# Dveri_Termotunnel.net
KiCad netlist of a schematic drawn in EAGLE
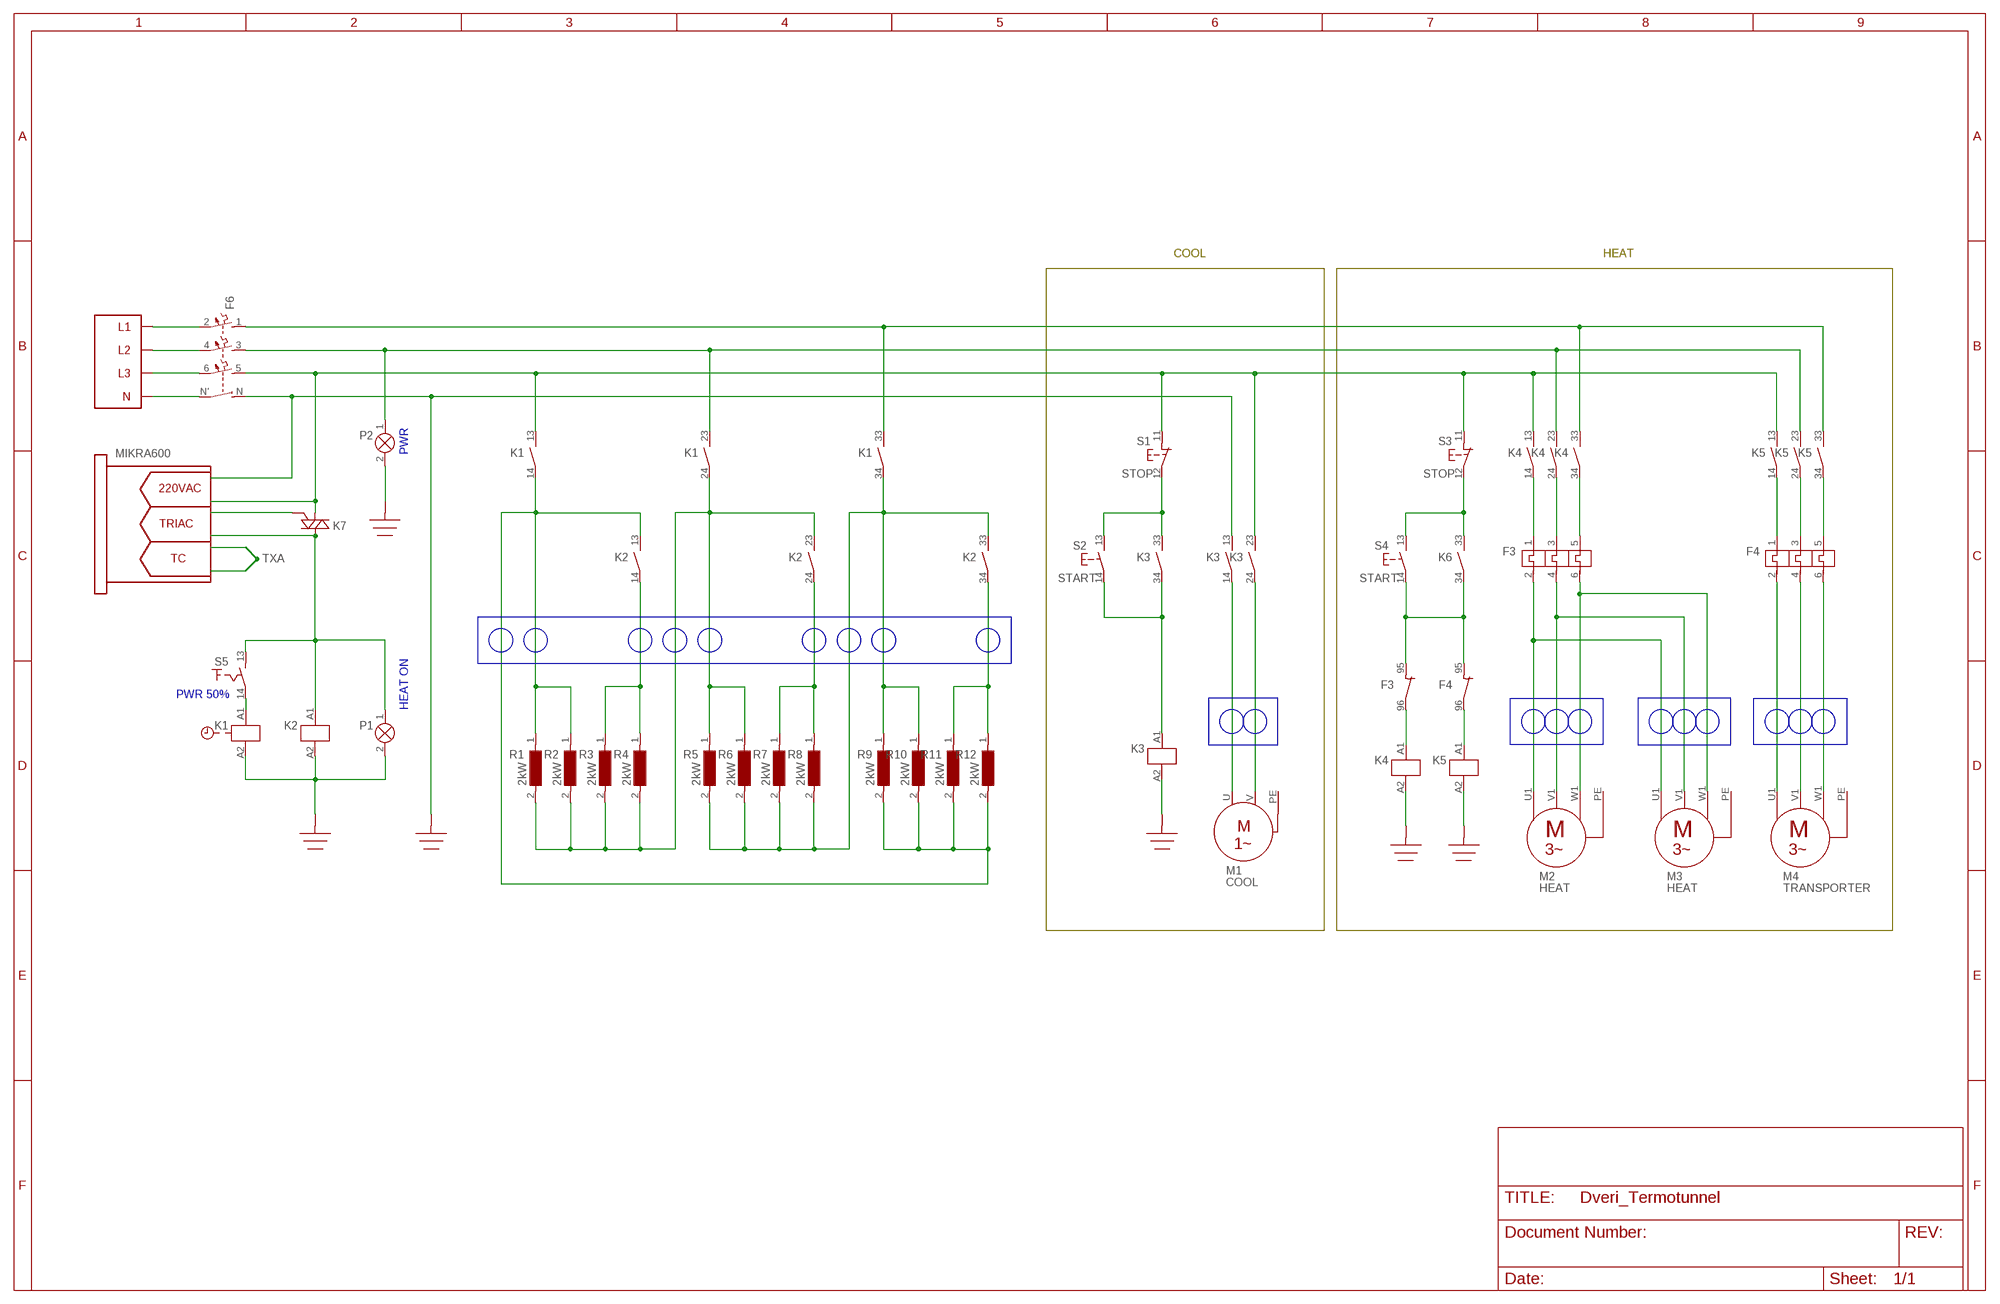
[diagram p0: schematic, sheet 1]

(export (version "E")
  (design (tool "Eeschema 10.0.6"))
  (components
    (comp (ref "F3")
      (value "MOTORSCHUTZSCHALTER_3-POL_THERM_AUSLOESUNG_HILFSKONTAKTE")
      (footprint "eagle-import:MOTORSCHUTZSCHALTER_3-POL_THERM_AUSLOESUNG_HILFSKONTAKT_95_96_97_98")
      (libsource (lib "eagle-import") (part "MOTORSCHUTZSCHALTER_3-POL_THERM_AUSLOESUNG_HILFSKONTAKTE"))
    )
    (comp (ref "F4")
      (value "MOTORSCHUTZSCHALTER_3-POL_THERM_AUSLOESUNG_HILFSKONTAKTE")
      (footprint "eagle-import:MOTORSCHUTZSCHALTER_3-POL_THERM_AUSLOESUNG_HILFSKONTAKT_95_96_97_98")
      (libsource (lib "eagle-import") (part "MOTORSCHUTZSCHALTER_3-POL_THERM_AUSLOESUNG_HILFSKONTAKTE"))
    )
    (comp (ref "F6")
      (value "LEITUNGSSCHUTZSCHALTER_4-POL")
      (footprint "eagle-import:LEITUNGSSCHUTZSCHALTER_4-POL")
      (libsource (lib "eagle-import") (part "LEITUNGSSCHUTZSCHALTER_4-POL"))
    )
    (comp (ref "K1")
      (value "HILFSSCHUETZ_13-14_23-24_33_34")
      (footprint "eagle-import:HILFSSCHUETZ_13-14_23-24_33_34")
      (libsource (lib "eagle-import") (part "HILFSSCHUETZ_13-14_23-24_33_34"))
    )
    (comp (ref "K2")
      (value "HILFSSCHUETZ_13-14_23-24_33_34")
      (footprint "eagle-import:HILFSSCHUETZ_13-14_23-24_33_34")
      (libsource (lib "eagle-import") (part "HILFSSCHUETZ_13-14_23-24_33_34"))
    )
    (comp (ref "K3")
      (value "HILFSSCHUETZ_13-14_23-24_33_34")
      (footprint "eagle-import:HILFSSCHUETZ_13-14_23-24_33_34")
      (libsource (lib "eagle-import") (part "HILFSSCHUETZ_13-14_23-24_33_34"))
    )
    (comp (ref "K4")
      (value "HILFSSCHUETZ_13-14_23-24_33_34")
      (footprint "eagle-import:HILFSSCHUETZ_13-14_23-24_33_34")
      (libsource (lib "eagle-import") (part "HILFSSCHUETZ_13-14_23-24_33_34"))
    )
    (comp (ref "K5")
      (value "HILFSSCHUETZ_13-14_23-24_33_34")
      (footprint "eagle-import:HILFSSCHUETZ_13-14_23-24_33_34")
      (libsource (lib "eagle-import") (part "HILFSSCHUETZ_13-14_23-24_33_34"))
    )
    (comp (ref "K6")
      (value "HILFSSCHUETZ_13-14_23-24_33_34")
      (footprint "eagle-import:HILFSSCHUETZ_13-14_23-24_33_34")
      (libsource (lib "eagle-import") (part "HILFSSCHUETZ_13-14_23-24_33_34"))
    )
    (comp (ref "K7")
      (value "TRIAC")
      (footprint "eagle-import:TRIAC")
      (libsource (lib "eagle-import") (part "TRIAC"))
    )
    (comp (ref "M1")
      (value "COOL")
      (footprint "eagle-import:MOTOR_1-PHASEN")
      (libsource (lib "eagle-import") (part "MOTOR_1-PHASEN"))
    )
    (comp (ref "M2")
      (value "HEAT")
      (footprint "eagle-import:MOTOR_3-POL_PE")
      (libsource (lib "eagle-import") (part "MOTOR_3-POL_PE"))
    )
    (comp (ref "M3")
      (value "HEAT")
      (footprint "eagle-import:MOTOR_3-POL_PE")
      (libsource (lib "eagle-import") (part "MOTOR_3-POL_PE"))
    )
    (comp (ref "M4")
      (value "TRANSPORTER")
      (footprint "eagle-import:MOTOR_3-POL_PE")
      (libsource (lib "eagle-import") (part "MOTOR_3-POL_PE"))
    )
    (comp (ref "P1")
      (value "SIGNALLAMPE")
      (footprint "eagle-import:LAMPE")
      (libsource (lib "eagle-import") (part "SIGNALLAMPE"))
    )
    (comp (ref "P2")
      (value "SIGNALLAMPE")
      (footprint "eagle-import:LAMPE")
      (libsource (lib "eagle-import") (part "SIGNALLAMPE"))
    )
    (comp (ref "R1")
      (value "2kW")
      (footprint "eagle-import:WICKLUNG")
      (libsource (lib "eagle-import") (part "SPULE"))
    )
    (comp (ref "R2")
      (value "2kW")
      (footprint "eagle-import:WICKLUNG")
      (libsource (lib "eagle-import") (part "SPULE"))
    )
    (comp (ref "R3")
      (value "2kW")
      (footprint "eagle-import:WICKLUNG")
      (libsource (lib "eagle-import") (part "SPULE"))
    )
    (comp (ref "R4")
      (value "2kW")
      (footprint "eagle-import:WICKLUNG")
      (libsource (lib "eagle-import") (part "SPULE"))
    )
    (comp (ref "R5")
      (value "2kW")
      (footprint "eagle-import:WICKLUNG")
      (libsource (lib "eagle-import") (part "SPULE"))
    )
    (comp (ref "R6")
      (value "2kW")
      (footprint "eagle-import:WICKLUNG")
      (libsource (lib "eagle-import") (part "SPULE"))
    )
    (comp (ref "R7")
      (value "2kW")
      (footprint "eagle-import:WICKLUNG")
      (libsource (lib "eagle-import") (part "SPULE"))
    )
    (comp (ref "R8")
      (value "2kW")
      (footprint "eagle-import:WICKLUNG")
      (libsource (lib "eagle-import") (part "SPULE"))
    )
    (comp (ref "R9")
      (value "2kW")
      (footprint "eagle-import:WICKLUNG")
      (libsource (lib "eagle-import") (part "SPULE"))
    )
    (comp (ref "R10")
      (value "2kW")
      (footprint "eagle-import:WICKLUNG")
      (libsource (lib "eagle-import") (part "SPULE"))
    )
    (comp (ref "R11")
      (value "2kW")
      (footprint "eagle-import:WICKLUNG")
      (libsource (lib "eagle-import") (part "SPULE"))
    )
    (comp (ref "R12")
      (value "2kW")
      (footprint "eagle-import:WICKLUNG")
      (libsource (lib "eagle-import") (part "SPULE"))
    )
    (comp (ref "S1")
      (value "OEFFNER_TASTSCHALTER")
      (footprint "eagle-import:OEFFNER_TASTSCHALTER")
      (libsource (lib "eagle-import") (part "OEFFNER_TASTSCHALTER"))
    )
    (comp (ref "S2")
      (value "SCHLIESSER_TASTSCHALTER")
      (footprint "eagle-import:SCHLIESSER_TASTSCHALTER")
      (libsource (lib "eagle-import") (part "SCHLIESSER_TASTSCHALTER"))
    )
    (comp (ref "S3")
      (value "OEFFNER_TASTSCHALTER")
      (footprint "eagle-import:OEFFNER_TASTSCHALTER")
      (libsource (lib "eagle-import") (part "OEFFNER_TASTSCHALTER"))
    )
    (comp (ref "S4")
      (value "SCHLIESSER_TASTSCHALTER")
      (footprint "eagle-import:SCHLIESSER_TASTSCHALTER")
      (libsource (lib "eagle-import") (part "SCHLIESSER_TASTSCHALTER"))
    )
    (comp (ref "S5")
      (value "KIPPSCHALTER_AUS")
      (footprint "eagle-import:EINTASTER")
      (libsource (lib "eagle-import") (part "KIPPSCHALTER_AUS"))
    )
    (comp (ref "X1")
      (value "ERDE_ALLGEMEIN")
      (footprint "eagle-import:ERDE_ALLGEMEIN")
      (libsource (lib "eagle-import") (part "ERDE_ALLGEMEIN"))
    )
    (comp (ref "X2")
      (value "ERDE_ALLGEMEIN")
      (footprint "eagle-import:ERDE_ALLGEMEIN")
      (libsource (lib "eagle-import") (part "ERDE_ALLGEMEIN"))
    )
    (comp (ref "X3")
      (value "ERDE_ALLGEMEIN")
      (footprint "eagle-import:ERDE_ALLGEMEIN")
      (libsource (lib "eagle-import") (part "ERDE_ALLGEMEIN"))
    )
    (comp (ref "X4")
      (value "ERDE_ALLGEMEIN")
      (footprint "eagle-import:ERDE_ALLGEMEIN")
      (libsource (lib "eagle-import") (part "ERDE_ALLGEMEIN"))
    )
    (comp (ref "X5")
      (value "ERDE_ALLGEMEIN")
      (footprint "eagle-import:ERDE_ALLGEMEIN")
      (libsource (lib "eagle-import") (part "ERDE_ALLGEMEIN"))
    )
    (comp (ref "X6")
      (value "ERDE_ALLGEMEIN")
      (footprint "eagle-import:ERDE_ALLGEMEIN")
      (libsource (lib "eagle-import") (part "ERDE_ALLGEMEIN"))
    )
  )
  (nets
    (net (code "1") (name "Net-(F3-Pad2)") (class "Default")
      (node (ref "F3") (pin "2") (pinfunction "2_2") (pintype "passive"))
      (node (ref "M2") (pin "U1") (pinfunction "U1_U1") (pintype "passive"))
      (node (ref "M3") (pin "U1") (pinfunction "U1_U1") (pintype "passive"))
    )
    (net (code "2") (name "Net-(F3-Pad4)") (class "Default")
      (node (ref "F3") (pin "4") (pinfunction "4_4") (pintype "passive"))
      (node (ref "M2") (pin "V1") (pinfunction "V1_V1") (pintype "passive"))
      (node (ref "M3") (pin "V1") (pinfunction "V1_V1") (pintype "passive"))
    )
    (net (code "3") (name "Net-(F3-Pad6)") (class "Default")
      (node (ref "F3") (pin "6") (pinfunction "6_6") (pintype "passive"))
      (node (ref "M2") (pin "W1") (pinfunction "W1_W1") (pintype "passive"))
      (node (ref "M3") (pin "W1") (pinfunction "W1_W1") (pintype "passive"))
    )
    (net (code "4") (name "Net-(F3-Pad96)") (class "Default")
      (node (ref "F3") (pin "96") (pinfunction "96_96") (pintype "passive"))
      (node (ref "K4") (pin "A1") (pinfunction "A1_A1") (pintype "input"))
    )
    (net (code "5") (name "Net-(F4-Pad2)") (class "Default")
      (node (ref "F4") (pin "2") (pinfunction "2_2") (pintype "passive"))
      (node (ref "M4") (pin "U1") (pinfunction "U1_U1") (pintype "passive"))
    )
    (net (code "6") (name "Net-(F4-Pad4)") (class "Default")
      (node (ref "F4") (pin "4") (pinfunction "4_4") (pintype "passive"))
      (node (ref "M4") (pin "V1") (pinfunction "V1_V1") (pintype "passive"))
    )
    (net (code "7") (name "Net-(F4-Pad6)") (class "Default")
      (node (ref "F4") (pin "6") (pinfunction "6_6") (pintype "passive"))
      (node (ref "M4") (pin "W1") (pinfunction "W1_W1") (pintype "passive"))
    )
    (net (code "8") (name "Net-(F4-Pad96)") (class "Default")
      (node (ref "F4") (pin "96") (pinfunction "96_96") (pintype "passive"))
      (node (ref "K5") (pin "A1") (pinfunction "A1_A1") (pintype "input"))
    )
    (net (code "9") (name "Net-(F6-N-PadN')") (class "Default")
      (node (ref "F6") (pin "N'") (pinfunction "N_N'") (pintype "passive"))
    )
    (net (code "10") (name "Net-(F6-Pad2)") (class "Default")
      (node (ref "F6") (pin "2") (pinfunction "2_2") (pintype "passive"))
    )
    (net (code "11") (name "Net-(F6-Pad4)") (class "Default")
      (node (ref "F6") (pin "4") (pinfunction "4_4") (pintype "passive"))
    )
    (net (code "12") (name "Net-(F6-Pad6)") (class "Default")
      (node (ref "F6") (pin "6") (pinfunction "6_6") (pintype "passive"))
    )
    (net (code "13") (name "Net-(K1A-3)") (class "Default")
      (node (ref "F6") (pin "5") (pinfunction "5_5") (pintype "passive"))
      (node (ref "K1") (pin "13") (pinfunction "3_13") (pintype "passive"))
      (node (ref "K3") (pin "23") (pinfunction "3_23") (pintype "passive"))
      (node (ref "K4") (pin "13") (pinfunction "3_13") (pintype "passive"))
      (node (ref "K5") (pin "13") (pinfunction "3_13") (pintype "passive"))
      (node (ref "K7") (pin "A2") (pinfunction "A2_A2") (pintype "passive"))
      (node (ref "S1") (pin "11") (pinfunction "1_11") (pintype "input"))
      (node (ref "S3") (pin "11") (pinfunction "1_11") (pintype "input"))
    )
    (net (code "14") (name "Net-(K1A-4)") (class "Default")
      (node (ref "K1") (pin "14") (pinfunction "4_14") (pintype "passive"))
      (node (ref "K2") (pin "13") (pinfunction "3_13") (pintype "passive"))
      (node (ref "R1") (pin "1") (pinfunction "1_1") (pintype "passive"))
      (node (ref "R10") (pin "2") (pinfunction "2_2") (pintype "passive"))
      (node (ref "R11") (pin "2") (pinfunction "2_2") (pintype "passive"))
      (node (ref "R12") (pin "2") (pinfunction "2_2") (pintype "passive"))
      (node (ref "R2") (pin "1") (pinfunction "1_1") (pintype "passive"))
      (node (ref "R9") (pin "2") (pinfunction "2_2") (pintype "passive"))
    )
    (net (code "15") (name "Net-(K1B-3)") (class "Default")
      (node (ref "F6") (pin "3") (pinfunction "3_3") (pintype "passive"))
      (node (ref "K1") (pin "23") (pinfunction "3_23") (pintype "passive"))
      (node (ref "K4") (pin "23") (pinfunction "3_23") (pintype "passive"))
      (node (ref "K5") (pin "23") (pinfunction "3_23") (pintype "passive"))
      (node (ref "P2") (pin "1") (pinfunction "X1_1") (pintype "passive"))
    )
    (net (code "16") (name "Net-(K1B-4)") (class "Default")
      (node (ref "K1") (pin "24") (pinfunction "4_24") (pintype "passive"))
      (node (ref "K2") (pin "23") (pinfunction "3_23") (pintype "passive"))
      (node (ref "R1") (pin "2") (pinfunction "2_2") (pintype "passive"))
      (node (ref "R2") (pin "2") (pinfunction "2_2") (pintype "passive"))
      (node (ref "R3") (pin "2") (pinfunction "2_2") (pintype "passive"))
      (node (ref "R4") (pin "2") (pinfunction "2_2") (pintype "passive"))
      (node (ref "R5") (pin "1") (pinfunction "1_1") (pintype "passive"))
      (node (ref "R6") (pin "1") (pinfunction "1_1") (pintype "passive"))
    )
    (net (code "17") (name "Net-(K1C-3)") (class "Default")
      (node (ref "F6") (pin "1") (pinfunction "1_1") (pintype "passive"))
      (node (ref "K1") (pin "33") (pinfunction "3_33") (pintype "passive"))
      (node (ref "K4") (pin "33") (pinfunction "3_33") (pintype "passive"))
      (node (ref "K5") (pin "33") (pinfunction "3_33") (pintype "passive"))
    )
    (net (code "18") (name "Net-(K1C-4)") (class "Default")
      (node (ref "K1") (pin "34") (pinfunction "4_34") (pintype "passive"))
      (node (ref "K2") (pin "33") (pinfunction "3_33") (pintype "passive"))
      (node (ref "R10") (pin "1") (pinfunction "1_1") (pintype "passive"))
      (node (ref "R5") (pin "2") (pinfunction "2_2") (pintype "passive"))
      (node (ref "R6") (pin "2") (pinfunction "2_2") (pintype "passive"))
      (node (ref "R7") (pin "2") (pinfunction "2_2") (pintype "passive"))
      (node (ref "R8") (pin "2") (pinfunction "2_2") (pintype "passive"))
      (node (ref "R9") (pin "1") (pinfunction "1_1") (pintype "passive"))
    )
    (net (code "19") (name "Net-(K2A-4)") (class "Default")
      (node (ref "K2") (pin "14") (pinfunction "4_14") (pintype "passive"))
      (node (ref "R3") (pin "1") (pinfunction "1_1") (pintype "passive"))
      (node (ref "R4") (pin "1") (pinfunction "1_1") (pintype "passive"))
    )
    (net (code "20") (name "Net-(K2B-4)") (class "Default")
      (node (ref "K2") (pin "24") (pinfunction "4_24") (pintype "passive"))
      (node (ref "R7") (pin "1") (pinfunction "1_1") (pintype "passive"))
      (node (ref "R8") (pin "1") (pinfunction "1_1") (pintype "passive"))
    )
    (net (code "21") (name "Net-(K2C-4)") (class "Default")
      (node (ref "K2") (pin "34") (pinfunction "4_34") (pintype "passive"))
      (node (ref "R11") (pin "1") (pinfunction "1_1") (pintype "passive"))
      (node (ref "R12") (pin "1") (pinfunction "1_1") (pintype "passive"))
    )
    (net (code "22") (name "Net-(K3A-3)") (class "Default")
      (node (ref "F6") (pin "N") (pinfunction "N_N") (pintype "passive"))
      (node (ref "K3") (pin "13") (pinfunction "3_13") (pintype "passive"))
      (node (ref "X1") (pin "1") (pinfunction "PE_1") (pintype "passive"))
    )
    (net (code "23") (name "Net-(K3A-4)") (class "Default")
      (node (ref "K3") (pin "14") (pinfunction "4_14") (pintype "passive"))
      (node (ref "M1") (pin "U") (pinfunction "U_U") (pintype "passive"))
    )
    (net (code "24") (name "Net-(K3B-4)") (class "Default")
      (node (ref "K3") (pin "24") (pinfunction "4_24") (pintype "passive"))
      (node (ref "M1") (pin "V") (pinfunction "V_V") (pintype "passive"))
    )
    (net (code "25") (name "Net-(K3C-3)") (class "Default")
      (node (ref "K3") (pin "33") (pinfunction "3_33") (pintype "passive"))
      (node (ref "S1") (pin "12") (pinfunction "2_12") (pintype "input"))
      (node (ref "S2") (pin "13") (pinfunction "3_13") (pintype "input"))
    )
    (net (code "26") (name "Net-(K3C-4)") (class "Default")
      (node (ref "K3") (pin "34") (pinfunction "4_34") (pintype "passive"))
      (node (ref "K3") (pin "A1") (pinfunction "A1_A1") (pintype "input"))
      (node (ref "S2") (pin "14") (pinfunction "4_14") (pintype "input"))
    )
    (net (code "27") (name "Net-(K4A-4)") (class "Default")
      (node (ref "F3") (pin "1") (pinfunction "1_1") (pintype "passive"))
      (node (ref "K4") (pin "14") (pinfunction "4_14") (pintype "passive"))
    )
    (net (code "28") (name "Net-(K4B-4)") (class "Default")
      (node (ref "F3") (pin "3") (pinfunction "3_3") (pintype "passive"))
      (node (ref "K4") (pin "24") (pinfunction "4_24") (pintype "passive"))
    )
    (net (code "29") (name "Net-(K4C-4)") (class "Default")
      (node (ref "F3") (pin "5") (pinfunction "5_5") (pintype "passive"))
      (node (ref "K4") (pin "34") (pinfunction "4_34") (pintype "passive"))
    )
    (net (code "30") (name "Net-(K5A-4)") (class "Default")
      (node (ref "F4") (pin "1") (pinfunction "1_1") (pintype "passive"))
      (node (ref "K5") (pin "14") (pinfunction "4_14") (pintype "passive"))
    )
    (net (code "31") (name "Net-(K5B-4)") (class "Default")
      (node (ref "F4") (pin "3") (pinfunction "3_3") (pintype "passive"))
      (node (ref "K5") (pin "24") (pinfunction "4_24") (pintype "passive"))
    )
    (net (code "32") (name "Net-(K5C-4)") (class "Default")
      (node (ref "F4") (pin "5") (pinfunction "5_5") (pintype "passive"))
      (node (ref "K5") (pin "34") (pinfunction "4_34") (pintype "passive"))
    )
    (net (code "33") (name "Net-(K6C-3)") (class "Default")
      (node (ref "K6") (pin "33") (pinfunction "3_33") (pintype "passive"))
      (node (ref "S3") (pin "12") (pinfunction "2_12") (pintype "input"))
      (node (ref "S4") (pin "13") (pinfunction "3_13") (pintype "input"))
    )
    (net (code "34") (name "Net-(K6C-4)") (class "Default")
      (node (ref "F3") (pin "95") (pinfunction "95_95") (pintype "passive"))
      (node (ref "F4") (pin "95") (pinfunction "95_95") (pintype "passive"))
      (node (ref "K6") (pin "34") (pinfunction "4_34") (pintype "passive"))
      (node (ref "S4") (pin "14") (pinfunction "4_14") (pintype "input"))
    )
    (net (code "35") (name "Net-(P1-X1)") (class "Default")
      (node (ref "K2") (pin "A1") (pinfunction "A1_A1") (pintype "input"))
      (node (ref "K7") (pin "A1") (pinfunction "A1_A1") (pintype "passive"))
      (node (ref "P1") (pin "1") (pinfunction "X1_1") (pintype "passive"))
      (node (ref "S5") (pin "13") (pinfunction "3_13") (pintype "passive"))
    )
    (net (code "36") (name "Net-(P1-X2)") (class "Default")
      (node (ref "K1") (pin "A2") (pinfunction "A2_A2") (pintype "input"))
      (node (ref "K2") (pin "A2") (pinfunction "A2_A2") (pintype "input"))
      (node (ref "P1") (pin "2") (pinfunction "X2_2") (pintype "passive"))
      (node (ref "X2") (pin "1") (pinfunction "PE_1") (pintype "passive"))
    )
    (net (code "37") (name "Net-(P2-X2)") (class "Default")
      (node (ref "P2") (pin "2") (pinfunction "X2_2") (pintype "passive"))
      (node (ref "X6") (pin "1") (pinfunction "PE_1") (pintype "passive"))
    )
    (net (code "38") (name "Net-(S5-4)") (class "Default")
      (node (ref "K1") (pin "A1") (pinfunction "A1_A1") (pintype "input"))
      (node (ref "S5") (pin "14") (pinfunction "4_14") (pintype "passive"))
    )
    (net (code "39") (name "Net-(X3-PE)") (class "Default")
      (node (ref "K3") (pin "A2") (pinfunction "A2_A2") (pintype "input"))
      (node (ref "X3") (pin "1") (pinfunction "PE_1") (pintype "passive"))
    )
    (net (code "40") (name "Net-(X4-PE)") (class "Default")
      (node (ref "K4") (pin "A2") (pinfunction "A2_A2") (pintype "input"))
      (node (ref "X4") (pin "1") (pinfunction "PE_1") (pintype "passive"))
    )
    (net (code "41") (name "Net-(X5-PE)") (class "Default")
      (node (ref "K5") (pin "A2") (pinfunction "A2_A2") (pintype "input"))
      (node (ref "X5") (pin "1") (pinfunction "PE_1") (pintype "passive"))
    )
    (net (code "42") (name "unconnected-(K7-PadG)") (class "Default")
      (node (ref "K7") (pin "G") (pinfunction "G_G") (pintype "passive"))
    )
    (net (code "43") (name "unconnected-(M1-PadPE)") (class "Default")
      (node (ref "M1") (pin "PE") (pinfunction "PE_PE") (pintype "passive"))
    )
    (net (code "44") (name "unconnected-(M2-PadPE)") (class "Default")
      (node (ref "M2") (pin "PE") (pinfunction "PE_PE") (pintype "passive"))
    )
    (net (code "45") (name "unconnected-(M3-PadPE)") (class "Default")
      (node (ref "M3") (pin "PE") (pinfunction "PE_PE") (pintype "passive"))
    )
    (net (code "46") (name "unconnected-(M4-PadPE)") (class "Default")
      (node (ref "M4") (pin "PE") (pinfunction "PE_PE") (pintype "passive"))
    )
  )
)
